# 8_CAN.net
KiCad netlist of a schematic drawn in EAGLE
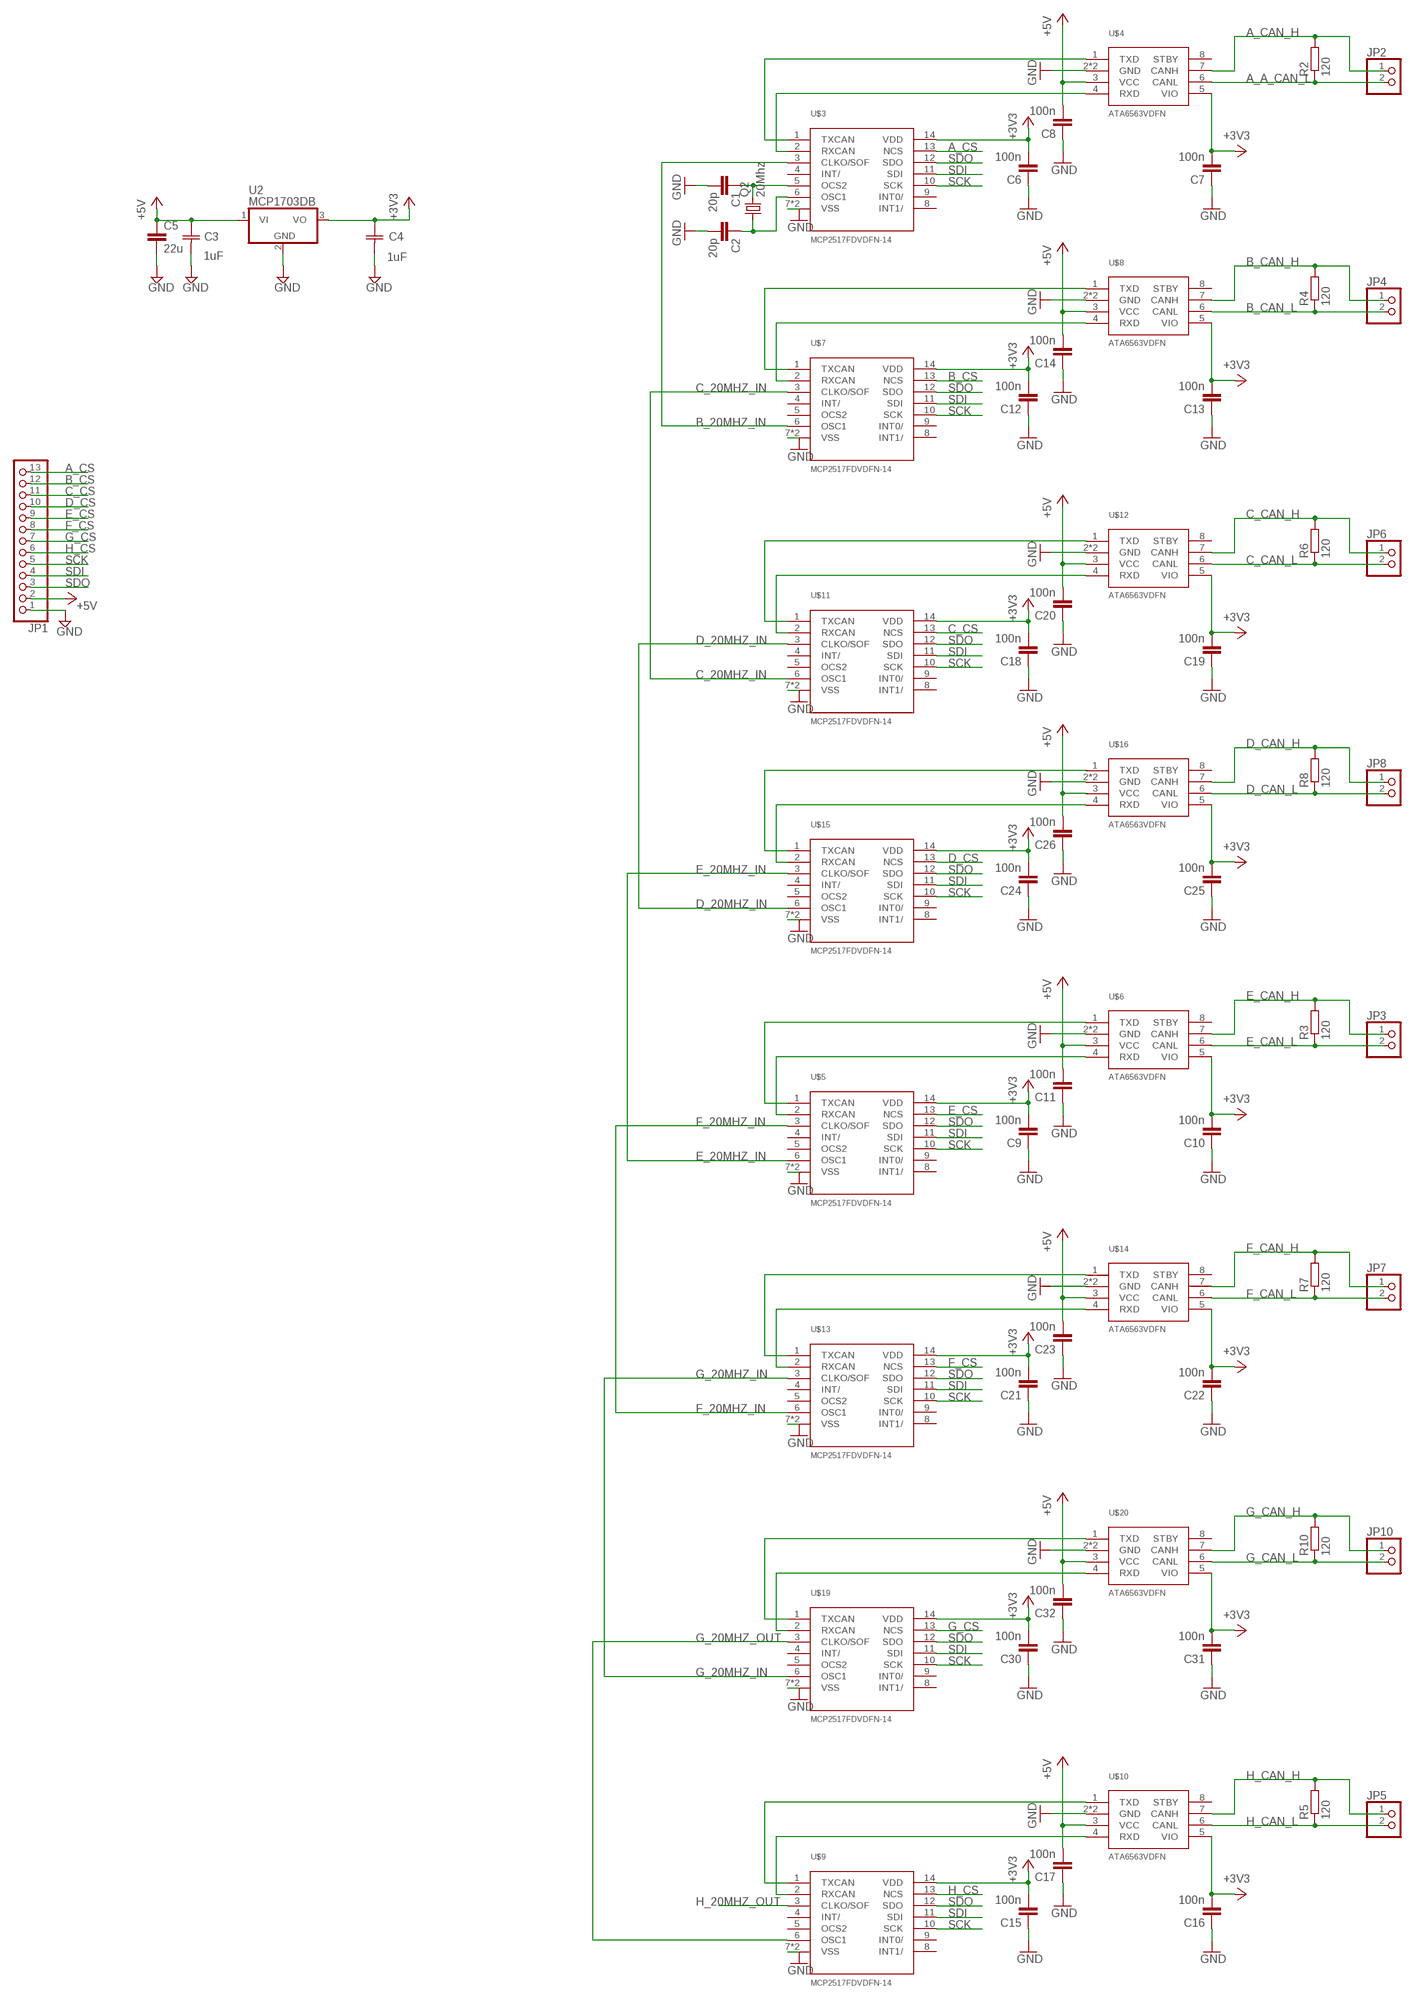
[diagram p0: schematic, sheet 1]

(export (version "E")
  (design (tool "Eeschema 10.0.6"))
  (components
    (comp (ref "C1")
      (value "20p")
      (footprint "eagle-import:C0402")
      (libsource (lib "eagle-import") (part "resistor_348_C-EUC0402"))
    )
    (comp (ref "C2")
      (value "20p")
      (footprint "eagle-import:C0402")
      (libsource (lib "eagle-import") (part "resistor_348_C-EUC0402"))
    )
    (comp (ref "C3")
      (value "1uF")
      (footprint "eagle-import:CAPC2013X140N")
      (fields (field (name "MPN") "C0805C105K3RACTU") (field (name "TOLERANCE") "±10%"))
      (libsource (lib "eagle-import") (part "C0805C105K3RACTU"))
    )
    (comp (ref "C4")
      (value "1uF")
      (footprint "eagle-import:CAPC2013X140N")
      (fields (field (name "MPN") "C0805C105K3RACTU") (field (name "TOLERANCE") "±10%"))
      (libsource (lib "eagle-import") (part "C0805C105K3RACTU"))
    )
    (comp (ref "C5")
      (value "22u")
      (footprint "eagle-import:C1206")
      (libsource (lib "eagle-import") (part "C-EUC1206"))
    )
    (comp (ref "C6")
      (value "100n")
      (footprint "eagle-import:C0402")
      (libsource (lib "eagle-import") (part "resistor_348_C-EUC0402"))
    )
    (comp (ref "C7")
      (value "100n")
      (footprint "eagle-import:C0402")
      (libsource (lib "eagle-import") (part "resistor_348_C-EUC0402"))
    )
    (comp (ref "C8")
      (value "100n")
      (footprint "eagle-import:C0402")
      (libsource (lib "eagle-import") (part "resistor_348_C-EUC0402"))
    )
    (comp (ref "C9")
      (value "100n")
      (footprint "eagle-import:C0402")
      (libsource (lib "eagle-import") (part "resistor_348_C-EUC0402"))
    )
    (comp (ref "C10")
      (value "100n")
      (footprint "eagle-import:C0402")
      (libsource (lib "eagle-import") (part "resistor_348_C-EUC0402"))
    )
    (comp (ref "C11")
      (value "100n")
      (footprint "eagle-import:C0402")
      (libsource (lib "eagle-import") (part "resistor_348_C-EUC0402"))
    )
    (comp (ref "C12")
      (value "100n")
      (footprint "eagle-import:C0402")
      (libsource (lib "eagle-import") (part "resistor_348_C-EUC0402"))
    )
    (comp (ref "C13")
      (value "100n")
      (footprint "eagle-import:C0402")
      (libsource (lib "eagle-import") (part "resistor_348_C-EUC0402"))
    )
    (comp (ref "C14")
      (value "100n")
      (footprint "eagle-import:C0402")
      (libsource (lib "eagle-import") (part "resistor_348_C-EUC0402"))
    )
    (comp (ref "C15")
      (value "100n")
      (footprint "eagle-import:C0402")
      (libsource (lib "eagle-import") (part "resistor_348_C-EUC0402"))
    )
    (comp (ref "C16")
      (value "100n")
      (footprint "eagle-import:C0402")
      (libsource (lib "eagle-import") (part "resistor_348_C-EUC0402"))
    )
    (comp (ref "C17")
      (value "100n")
      (footprint "eagle-import:C0402")
      (libsource (lib "eagle-import") (part "resistor_348_C-EUC0402"))
    )
    (comp (ref "C18")
      (value "100n")
      (footprint "eagle-import:C0402")
      (libsource (lib "eagle-import") (part "resistor_348_C-EUC0402"))
    )
    (comp (ref "C19")
      (value "100n")
      (footprint "eagle-import:C0402")
      (libsource (lib "eagle-import") (part "resistor_348_C-EUC0402"))
    )
    (comp (ref "C20")
      (value "100n")
      (footprint "eagle-import:C0402")
      (libsource (lib "eagle-import") (part "resistor_348_C-EUC0402"))
    )
    (comp (ref "C21")
      (value "100n")
      (footprint "eagle-import:C0402")
      (libsource (lib "eagle-import") (part "resistor_348_C-EUC0402"))
    )
    (comp (ref "C22")
      (value "100n")
      (footprint "eagle-import:C0402")
      (libsource (lib "eagle-import") (part "resistor_348_C-EUC0402"))
    )
    (comp (ref "C23")
      (value "100n")
      (footprint "eagle-import:C0402")
      (libsource (lib "eagle-import") (part "resistor_348_C-EUC0402"))
    )
    (comp (ref "C24")
      (value "100n")
      (footprint "eagle-import:C0402")
      (libsource (lib "eagle-import") (part "resistor_348_C-EUC0402"))
    )
    (comp (ref "C25")
      (value "100n")
      (footprint "eagle-import:C0402")
      (libsource (lib "eagle-import") (part "resistor_348_C-EUC0402"))
    )
    (comp (ref "C26")
      (value "100n")
      (footprint "eagle-import:C0402")
      (libsource (lib "eagle-import") (part "resistor_348_C-EUC0402"))
    )
    (comp (ref "C30")
      (value "100n")
      (footprint "eagle-import:C0402")
      (libsource (lib "eagle-import") (part "resistor_348_C-EUC0402"))
    )
    (comp (ref "C31")
      (value "100n")
      (footprint "eagle-import:C0402")
      (libsource (lib "eagle-import") (part "resistor_348_C-EUC0402"))
    )
    (comp (ref "C32")
      (value "100n")
      (footprint "eagle-import:C0402")
      (libsource (lib "eagle-import") (part "resistor_348_C-EUC0402"))
    )
    (comp (ref "JP1")
      (value "PINHD-1X13")
      (footprint "eagle-import:1X13")
      (libsource (lib "eagle-import") (part "PINHD-1X13"))
    )
    (comp (ref "JP2")
      (value "PINHD-1X2")
      (footprint "eagle-import:1X02")
      (libsource (lib "eagle-import") (part "PINHD-1X2"))
    )
    (comp (ref "JP3")
      (value "PINHD-1X2")
      (footprint "eagle-import:1X02")
      (libsource (lib "eagle-import") (part "PINHD-1X2"))
    )
    (comp (ref "JP4")
      (value "PINHD-1X2")
      (footprint "eagle-import:1X02")
      (libsource (lib "eagle-import") (part "PINHD-1X2"))
    )
    (comp (ref "JP5")
      (value "PINHD-1X2")
      (footprint "eagle-import:1X02")
      (libsource (lib "eagle-import") (part "PINHD-1X2"))
    )
    (comp (ref "JP6")
      (value "PINHD-1X2")
      (footprint "eagle-import:1X02")
      (libsource (lib "eagle-import") (part "PINHD-1X2"))
    )
    (comp (ref "JP7")
      (value "PINHD-1X2")
      (footprint "eagle-import:1X02")
      (libsource (lib "eagle-import") (part "PINHD-1X2"))
    )
    (comp (ref "JP8")
      (value "PINHD-1X2")
      (footprint "eagle-import:1X02")
      (libsource (lib "eagle-import") (part "PINHD-1X2"))
    )
    (comp (ref "JP10")
      (value "PINHD-1X2")
      (footprint "eagle-import:1X02")
      (libsource (lib "eagle-import") (part "PINHD-1X2"))
    )
    (comp (ref "Q2")
      (value "20Mhz")
      (footprint "eagle-import:CTS406")
      (libsource (lib "eagle-import") (part "CRYSTALCTS406"))
    )
    (comp (ref "R2")
      (value "120")
      (footprint "eagle-import:R0402")
      (libsource (lib "eagle-import") (part "R-EU_R0402"))
    )
    (comp (ref "R3")
      (value "120")
      (footprint "eagle-import:R0402")
      (libsource (lib "eagle-import") (part "R-EU_R0402"))
    )
    (comp (ref "R4")
      (value "120")
      (footprint "eagle-import:R0402")
      (libsource (lib "eagle-import") (part "R-EU_R0402"))
    )
    (comp (ref "R5")
      (value "120")
      (footprint "eagle-import:R0402")
      (libsource (lib "eagle-import") (part "R-EU_R0402"))
    )
    (comp (ref "R6")
      (value "120")
      (footprint "eagle-import:R0402")
      (libsource (lib "eagle-import") (part "R-EU_R0402"))
    )
    (comp (ref "R7")
      (value "120")
      (footprint "eagle-import:R0402")
      (libsource (lib "eagle-import") (part "R-EU_R0402"))
    )
    (comp (ref "R8")
      (value "120")
      (footprint "eagle-import:R0402")
      (libsource (lib "eagle-import") (part "R-EU_R0402"))
    )
    (comp (ref "R10")
      (value "120")
      (footprint "eagle-import:R0402")
      (libsource (lib "eagle-import") (part "R-EU_R0402"))
    )
    (comp (ref "U$3")
      (value "MCP2517FDVDFN-14")
      (footprint "eagle-import:VDFN-14_4.5X3")
      (libsource (lib "eagle-import") (part "MCP2517FDVDFN-14"))
    )
    (comp (ref "U$4")
      (value "ATA6563VDFN")
      (footprint "eagle-import:VDFN-8_3X3")
      (libsource (lib "eagle-import") (part "ATA6563VDFN"))
    )
    (comp (ref "U$5")
      (value "MCP2517FDVDFN-14")
      (footprint "eagle-import:VDFN-14_4.5X3")
      (libsource (lib "eagle-import") (part "MCP2517FDVDFN-14"))
    )
    (comp (ref "U$6")
      (value "ATA6563VDFN")
      (footprint "eagle-import:VDFN-8_3X3")
      (libsource (lib "eagle-import") (part "ATA6563VDFN"))
    )
    (comp (ref "U$7")
      (value "MCP2517FDVDFN-14")
      (footprint "eagle-import:VDFN-14_4.5X3")
      (libsource (lib "eagle-import") (part "MCP2517FDVDFN-14"))
    )
    (comp (ref "U$8")
      (value "ATA6563VDFN")
      (footprint "eagle-import:VDFN-8_3X3")
      (libsource (lib "eagle-import") (part "ATA6563VDFN"))
    )
    (comp (ref "U$9")
      (value "MCP2517FDVDFN-14")
      (footprint "eagle-import:VDFN-14_4.5X3")
      (libsource (lib "eagle-import") (part "MCP2517FDVDFN-14"))
    )
    (comp (ref "U$10")
      (value "ATA6563VDFN")
      (footprint "eagle-import:VDFN-8_3X3")
      (libsource (lib "eagle-import") (part "ATA6563VDFN"))
    )
    (comp (ref "U$11")
      (value "MCP2517FDVDFN-14")
      (footprint "eagle-import:VDFN-14_4.5X3")
      (libsource (lib "eagle-import") (part "MCP2517FDVDFN-14"))
    )
    (comp (ref "U$12")
      (value "ATA6563VDFN")
      (footprint "eagle-import:VDFN-8_3X3")
      (libsource (lib "eagle-import") (part "ATA6563VDFN"))
    )
    (comp (ref "U$13")
      (value "MCP2517FDVDFN-14")
      (footprint "eagle-import:VDFN-14_4.5X3")
      (libsource (lib "eagle-import") (part "MCP2517FDVDFN-14"))
    )
    (comp (ref "U$14")
      (value "ATA6563VDFN")
      (footprint "eagle-import:VDFN-8_3X3")
      (libsource (lib "eagle-import") (part "ATA6563VDFN"))
    )
    (comp (ref "U$15")
      (value "MCP2517FDVDFN-14")
      (footprint "eagle-import:VDFN-14_4.5X3")
      (libsource (lib "eagle-import") (part "MCP2517FDVDFN-14"))
    )
    (comp (ref "U$16")
      (value "ATA6563VDFN")
      (footprint "eagle-import:VDFN-8_3X3")
      (libsource (lib "eagle-import") (part "ATA6563VDFN"))
    )
    (comp (ref "U$19")
      (value "MCP2517FDVDFN-14")
      (footprint "eagle-import:VDFN-14_4.5X3")
      (libsource (lib "eagle-import") (part "MCP2517FDVDFN-14"))
    )
    (comp (ref "U$20")
      (value "ATA6563VDFN")
      (footprint "eagle-import:VDFN-8_3X3")
      (libsource (lib "eagle-import") (part "ATA6563VDFN"))
    )
    (comp (ref "U2")
      (value "MCP1703DB")
      (footprint "eagle-import:SOT223")
      (libsource (lib "eagle-import") (part "MCP1703DB"))
    )
  )
  (nets
    (net (code "1") (name "+3V3") (class "Default")
      (node (ref "C10") (pin "2") (pinfunction "2_2") (pintype "passive"))
      (node (ref "C12") (pin "2") (pinfunction "2_2") (pintype "passive"))
      (node (ref "C13") (pin "2") (pinfunction "2_2") (pintype "passive"))
      (node (ref "C15") (pin "2") (pinfunction "2_2") (pintype "passive"))
      (node (ref "C16") (pin "2") (pinfunction "2_2") (pintype "passive"))
      (node (ref "C18") (pin "2") (pinfunction "2_2") (pintype "passive"))
      (node (ref "C19") (pin "2") (pinfunction "2_2") (pintype "passive"))
      (node (ref "C21") (pin "2") (pinfunction "2_2") (pintype "passive"))
      (node (ref "C22") (pin "2") (pinfunction "2_2") (pintype "passive"))
      (node (ref "C24") (pin "2") (pinfunction "2_2") (pintype "passive"))
      (node (ref "C25") (pin "2") (pinfunction "2_2") (pintype "passive"))
      (node (ref "C30") (pin "2") (pinfunction "2_2") (pintype "passive"))
      (node (ref "C31") (pin "2") (pinfunction "2_2") (pintype "passive"))
      (node (ref "C4") (pin "1") (pinfunction "C1_1") (pintype "passive"))
      (node (ref "C6") (pin "2") (pinfunction "2_2") (pintype "passive"))
      (node (ref "C7") (pin "2") (pinfunction "2_2") (pintype "passive"))
      (node (ref "C9") (pin "2") (pinfunction "2_2") (pintype "passive"))
      (node (ref "U$10") (pin "5") (pinfunction "VIO_5") (pintype "bidirectional"))
      (node (ref "U$11") (pin "14") (pinfunction "VDD_14") (pintype "bidirectional"))
      (node (ref "U$12") (pin "5") (pinfunction "VIO_5") (pintype "bidirectional"))
      (node (ref "U$13") (pin "14") (pinfunction "VDD_14") (pintype "bidirectional"))
      (node (ref "U$14") (pin "5") (pinfunction "VIO_5") (pintype "bidirectional"))
      (node (ref "U$15") (pin "14") (pinfunction "VDD_14") (pintype "bidirectional"))
      (node (ref "U$16") (pin "5") (pinfunction "VIO_5") (pintype "bidirectional"))
      (node (ref "U$19") (pin "14") (pinfunction "VDD_14") (pintype "bidirectional"))
      (node (ref "U$20") (pin "5") (pinfunction "VIO_5") (pintype "bidirectional"))
      (node (ref "U$3") (pin "14") (pinfunction "VDD_14") (pintype "bidirectional"))
      (node (ref "U$4") (pin "5") (pinfunction "VIO_5") (pintype "bidirectional"))
      (node (ref "U$5") (pin "14") (pinfunction "VDD_14") (pintype "bidirectional"))
      (node (ref "U$6") (pin "5") (pinfunction "VIO_5") (pintype "bidirectional"))
      (node (ref "U$7") (pin "14") (pinfunction "VDD_14") (pintype "bidirectional"))
      (node (ref "U$8") (pin "5") (pinfunction "VIO_5") (pintype "bidirectional"))
      (node (ref "U$9") (pin "14") (pinfunction "VDD_14") (pintype "bidirectional"))
      (node (ref "U2") (pin "3") (pinfunction "VO_3") (pintype "passive"))
    )
    (net (code "2") (name "+5V") (class "Default")
      (node (ref "C11") (pin "2") (pinfunction "2_2") (pintype "passive"))
      (node (ref "C14") (pin "2") (pinfunction "2_2") (pintype "passive"))
      (node (ref "C17") (pin "2") (pinfunction "2_2") (pintype "passive"))
      (node (ref "C20") (pin "2") (pinfunction "2_2") (pintype "passive"))
      (node (ref "C23") (pin "2") (pinfunction "2_2") (pintype "passive"))
      (node (ref "C26") (pin "2") (pinfunction "2_2") (pintype "passive"))
      (node (ref "C3") (pin "1") (pinfunction "C1_1") (pintype "passive"))
      (node (ref "C32") (pin "2") (pinfunction "2_2") (pintype "passive"))
      (node (ref "C5") (pin "1") (pinfunction "1_1") (pintype "passive"))
      (node (ref "C8") (pin "2") (pinfunction "2_2") (pintype "passive"))
      (node (ref "JP1") (pin "2") (pinfunction "2_2") (pintype "passive"))
      (node (ref "U$10") (pin "3") (pinfunction "VCC_3") (pintype "bidirectional"))
      (node (ref "U$12") (pin "3") (pinfunction "VCC_3") (pintype "bidirectional"))
      (node (ref "U$14") (pin "3") (pinfunction "VCC_3") (pintype "bidirectional"))
      (node (ref "U$16") (pin "3") (pinfunction "VCC_3") (pintype "bidirectional"))
      (node (ref "U$20") (pin "3") (pinfunction "VCC_3") (pintype "bidirectional"))
      (node (ref "U$4") (pin "3") (pinfunction "VCC_3") (pintype "bidirectional"))
      (node (ref "U$6") (pin "3") (pinfunction "VCC_3") (pintype "bidirectional"))
      (node (ref "U$8") (pin "3") (pinfunction "VCC_3") (pintype "bidirectional"))
      (node (ref "U2") (pin "1") (pinfunction "VI_1") (pintype "input"))
    )
    (net (code "3") (name "/A_A_CAN_L") (class "Default")
      (node (ref "JP2") (pin "2") (pinfunction "2_2") (pintype "passive"))
      (node (ref "R2") (pin "1") (pinfunction "1_1") (pintype "passive"))
      (node (ref "U$4") (pin "6") (pinfunction "CANL_6") (pintype "bidirectional"))
    )
    (net (code "4") (name "/A_CAN_H") (class "Default")
      (node (ref "JP2") (pin "1") (pinfunction "1_1") (pintype "passive"))
      (node (ref "R2") (pin "2") (pinfunction "2_2") (pintype "passive"))
      (node (ref "U$4") (pin "7") (pinfunction "CANH_7") (pintype "bidirectional"))
    )
    (net (code "5") (name "/A_CS") (class "Default")
      (node (ref "JP1") (pin "13") (pinfunction "13_13") (pintype "passive"))
      (node (ref "U$3") (pin "13") (pinfunction "NCS_13") (pintype "bidirectional"))
    )
    (net (code "6") (name "/B_20MHZ_IN") (class "Default")
      (node (ref "U$3") (pin "3") (pinfunction "CLKO/SOF_3") (pintype "bidirectional"))
      (node (ref "U$7") (pin "6") (pinfunction "OSC1_6") (pintype "bidirectional"))
    )
    (net (code "7") (name "/B_CAN_H") (class "Default")
      (node (ref "JP4") (pin "1") (pinfunction "1_1") (pintype "passive"))
      (node (ref "R4") (pin "2") (pinfunction "2_2") (pintype "passive"))
      (node (ref "U$8") (pin "7") (pinfunction "CANH_7") (pintype "bidirectional"))
    )
    (net (code "8") (name "/B_CAN_L") (class "Default")
      (node (ref "JP4") (pin "2") (pinfunction "2_2") (pintype "passive"))
      (node (ref "R4") (pin "1") (pinfunction "1_1") (pintype "passive"))
      (node (ref "U$8") (pin "6") (pinfunction "CANL_6") (pintype "bidirectional"))
    )
    (net (code "9") (name "/B_CS") (class "Default")
      (node (ref "JP1") (pin "12") (pinfunction "12_12") (pintype "passive"))
      (node (ref "U$7") (pin "13") (pinfunction "NCS_13") (pintype "bidirectional"))
    )
    (net (code "10") (name "/C_20MHZ_IN") (class "Default")
      (node (ref "U$11") (pin "6") (pinfunction "OSC1_6") (pintype "bidirectional"))
      (node (ref "U$7") (pin "3") (pinfunction "CLKO/SOF_3") (pintype "bidirectional"))
    )
    (net (code "11") (name "/C_CAN_H") (class "Default")
      (node (ref "JP6") (pin "1") (pinfunction "1_1") (pintype "passive"))
      (node (ref "R6") (pin "2") (pinfunction "2_2") (pintype "passive"))
      (node (ref "U$12") (pin "7") (pinfunction "CANH_7") (pintype "bidirectional"))
    )
    (net (code "12") (name "/C_CAN_L") (class "Default")
      (node (ref "JP6") (pin "2") (pinfunction "2_2") (pintype "passive"))
      (node (ref "R6") (pin "1") (pinfunction "1_1") (pintype "passive"))
      (node (ref "U$12") (pin "6") (pinfunction "CANL_6") (pintype "bidirectional"))
    )
    (net (code "13") (name "/C_CS") (class "Default")
      (node (ref "JP1") (pin "11") (pinfunction "11_11") (pintype "passive"))
      (node (ref "U$11") (pin "13") (pinfunction "NCS_13") (pintype "bidirectional"))
    )
    (net (code "14") (name "/D_20MHZ_IN") (class "Default")
      (node (ref "U$11") (pin "3") (pinfunction "CLKO/SOF_3") (pintype "bidirectional"))
      (node (ref "U$15") (pin "6") (pinfunction "OSC1_6") (pintype "bidirectional"))
    )
    (net (code "15") (name "/D_CAN_H") (class "Default")
      (node (ref "JP8") (pin "1") (pinfunction "1_1") (pintype "passive"))
      (node (ref "R8") (pin "2") (pinfunction "2_2") (pintype "passive"))
      (node (ref "U$16") (pin "7") (pinfunction "CANH_7") (pintype "bidirectional"))
    )
    (net (code "16") (name "/D_CAN_L") (class "Default")
      (node (ref "JP8") (pin "2") (pinfunction "2_2") (pintype "passive"))
      (node (ref "R8") (pin "1") (pinfunction "1_1") (pintype "passive"))
      (node (ref "U$16") (pin "6") (pinfunction "CANL_6") (pintype "bidirectional"))
    )
    (net (code "17") (name "/D_CS") (class "Default")
      (node (ref "JP1") (pin "10") (pinfunction "10_10") (pintype "passive"))
      (node (ref "U$15") (pin "13") (pinfunction "NCS_13") (pintype "bidirectional"))
    )
    (net (code "18") (name "/E_20MHZ_IN") (class "Default")
      (node (ref "U$15") (pin "3") (pinfunction "CLKO/SOF_3") (pintype "bidirectional"))
      (node (ref "U$5") (pin "6") (pinfunction "OSC1_6") (pintype "bidirectional"))
    )
    (net (code "19") (name "/E_CAN_H") (class "Default")
      (node (ref "JP3") (pin "1") (pinfunction "1_1") (pintype "passive"))
      (node (ref "R3") (pin "2") (pinfunction "2_2") (pintype "passive"))
      (node (ref "U$6") (pin "7") (pinfunction "CANH_7") (pintype "bidirectional"))
    )
    (net (code "20") (name "/E_CAN_L") (class "Default")
      (node (ref "JP3") (pin "2") (pinfunction "2_2") (pintype "passive"))
      (node (ref "R3") (pin "1") (pinfunction "1_1") (pintype "passive"))
      (node (ref "U$6") (pin "6") (pinfunction "CANL_6") (pintype "bidirectional"))
    )
    (net (code "21") (name "/E_CS") (class "Default")
      (node (ref "JP1") (pin "9") (pinfunction "9_9") (pintype "passive"))
      (node (ref "U$5") (pin "13") (pinfunction "NCS_13") (pintype "bidirectional"))
    )
    (net (code "22") (name "/F_20MHZ_IN") (class "Default")
      (node (ref "U$13") (pin "6") (pinfunction "OSC1_6") (pintype "bidirectional"))
      (node (ref "U$5") (pin "3") (pinfunction "CLKO/SOF_3") (pintype "bidirectional"))
    )
    (net (code "23") (name "/F_CAN_H") (class "Default")
      (node (ref "JP7") (pin "1") (pinfunction "1_1") (pintype "passive"))
      (node (ref "R7") (pin "2") (pinfunction "2_2") (pintype "passive"))
      (node (ref "U$14") (pin "7") (pinfunction "CANH_7") (pintype "bidirectional"))
    )
    (net (code "24") (name "/F_CAN_L") (class "Default")
      (node (ref "JP7") (pin "2") (pinfunction "2_2") (pintype "passive"))
      (node (ref "R7") (pin "1") (pinfunction "1_1") (pintype "passive"))
      (node (ref "U$14") (pin "6") (pinfunction "CANL_6") (pintype "bidirectional"))
    )
    (net (code "25") (name "/F_CS") (class "Default")
      (node (ref "JP1") (pin "8") (pinfunction "8_8") (pintype "passive"))
      (node (ref "U$13") (pin "13") (pinfunction "NCS_13") (pintype "bidirectional"))
    )
    (net (code "26") (name "/G_20MHZ_IN") (class "Default")
      (node (ref "U$13") (pin "3") (pinfunction "CLKO/SOF_3") (pintype "bidirectional"))
      (node (ref "U$19") (pin "6") (pinfunction "OSC1_6") (pintype "bidirectional"))
    )
    (net (code "27") (name "/G_20MHZ_OUT") (class "Default")
      (node (ref "U$19") (pin "3") (pinfunction "CLKO/SOF_3") (pintype "bidirectional"))
      (node (ref "U$9") (pin "6") (pinfunction "OSC1_6") (pintype "bidirectional"))
    )
    (net (code "28") (name "/G_CAN_H") (class "Default")
      (node (ref "JP10") (pin "1") (pinfunction "1_1") (pintype "passive"))
      (node (ref "R10") (pin "2") (pinfunction "2_2") (pintype "passive"))
      (node (ref "U$20") (pin "7") (pinfunction "CANH_7") (pintype "bidirectional"))
    )
    (net (code "29") (name "/G_CAN_L") (class "Default")
      (node (ref "JP10") (pin "2") (pinfunction "2_2") (pintype "passive"))
      (node (ref "R10") (pin "1") (pinfunction "1_1") (pintype "passive"))
      (node (ref "U$20") (pin "6") (pinfunction "CANL_6") (pintype "bidirectional"))
    )
    (net (code "30") (name "/G_CS") (class "Default")
      (node (ref "JP1") (pin "7") (pinfunction "7_7") (pintype "passive"))
      (node (ref "U$19") (pin "13") (pinfunction "NCS_13") (pintype "bidirectional"))
    )
    (net (code "31") (name "/H_20MHZ_OUT") (class "Default")
      (node (ref "U$9") (pin "3") (pinfunction "CLKO/SOF_3") (pintype "bidirectional"))
    )
    (net (code "32") (name "/H_CAN_H") (class "Default")
      (node (ref "JP5") (pin "1") (pinfunction "1_1") (pintype "passive"))
      (node (ref "R5") (pin "2") (pinfunction "2_2") (pintype "passive"))
      (node (ref "U$10") (pin "7") (pinfunction "CANH_7") (pintype "bidirectional"))
    )
    (net (code "33") (name "/H_CAN_L") (class "Default")
      (node (ref "JP5") (pin "2") (pinfunction "2_2") (pintype "passive"))
      (node (ref "R5") (pin "1") (pinfunction "1_1") (pintype "passive"))
      (node (ref "U$10") (pin "6") (pinfunction "CANL_6") (pintype "bidirectional"))
    )
    (net (code "34") (name "/H_CS") (class "Default")
      (node (ref "JP1") (pin "6") (pinfunction "6_6") (pintype "passive"))
      (node (ref "U$9") (pin "13") (pinfunction "NCS_13") (pintype "bidirectional"))
    )
    (net (code "35") (name "/SCK") (class "Default")
      (node (ref "JP1") (pin "5") (pinfunction "5_5") (pintype "passive"))
      (node (ref "U$11") (pin "10") (pinfunction "SCK_10") (pintype "bidirectional"))
      (node (ref "U$13") (pin "10") (pinfunction "SCK_10") (pintype "bidirectional"))
      (node (ref "U$15") (pin "10") (pinfunction "SCK_10") (pintype "bidirectional"))
      (node (ref "U$19") (pin "10") (pinfunction "SCK_10") (pintype "bidirectional"))
      (node (ref "U$3") (pin "10") (pinfunction "SCK_10") (pintype "bidirectional"))
      (node (ref "U$5") (pin "10") (pinfunction "SCK_10") (pintype "bidirectional"))
      (node (ref "U$7") (pin "10") (pinfunction "SCK_10") (pintype "bidirectional"))
      (node (ref "U$9") (pin "10") (pinfunction "SCK_10") (pintype "bidirectional"))
    )
    (net (code "36") (name "/SDI") (class "Default")
      (node (ref "JP1") (pin "4") (pinfunction "4_4") (pintype "passive"))
      (node (ref "U$11") (pin "11") (pinfunction "SDI_11") (pintype "bidirectional"))
      (node (ref "U$13") (pin "11") (pinfunction "SDI_11") (pintype "bidirectional"))
      (node (ref "U$15") (pin "11") (pinfunction "SDI_11") (pintype "bidirectional"))
      (node (ref "U$19") (pin "11") (pinfunction "SDI_11") (pintype "bidirectional"))
      (node (ref "U$3") (pin "11") (pinfunction "SDI_11") (pintype "bidirectional"))
      (node (ref "U$5") (pin "11") (pinfunction "SDI_11") (pintype "bidirectional"))
      (node (ref "U$7") (pin "11") (pinfunction "SDI_11") (pintype "bidirectional"))
      (node (ref "U$9") (pin "11") (pinfunction "SDI_11") (pintype "bidirectional"))
    )
    (net (code "37") (name "/SDO") (class "Default")
      (node (ref "JP1") (pin "3") (pinfunction "3_3") (pintype "passive"))
      (node (ref "U$11") (pin "12") (pinfunction "SDO_12") (pintype "bidirectional"))
      (node (ref "U$13") (pin "12") (pinfunction "SDO_12") (pintype "bidirectional"))
      (node (ref "U$15") (pin "12") (pinfunction "SDO_12") (pintype "bidirectional"))
      (node (ref "U$19") (pin "12") (pinfunction "SDO_12") (pintype "bidirectional"))
      (node (ref "U$3") (pin "12") (pinfunction "SDO_12") (pintype "bidirectional"))
      (node (ref "U$5") (pin "12") (pinfunction "SDO_12") (pintype "bidirectional"))
      (node (ref "U$7") (pin "12") (pinfunction "SDO_12") (pintype "bidirectional"))
      (node (ref "U$9") (pin "12") (pinfunction "SDO_12") (pintype "bidirectional"))
    )
    (net (code "38") (name "GND") (class "Default")
      (node (ref "C1") (pin "2") (pinfunction "2_2") (pintype "passive"))
      (node (ref "C10") (pin "1") (pinfunction "1_1") (pintype "passive"))
      (node (ref "C11") (pin "1") (pinfunction "1_1") (pintype "passive"))
      (node (ref "C12") (pin "1") (pinfunction "1_1") (pintype "passive"))
      (node (ref "C13") (pin "1") (pinfunction "1_1") (pintype "passive"))
      (node (ref "C14") (pin "1") (pinfunction "1_1") (pintype "passive"))
      (node (ref "C15") (pin "1") (pinfunction "1_1") (pintype "passive"))
      (node (ref "C16") (pin "1") (pinfunction "1_1") (pintype "passive"))
      (node (ref "C17") (pin "1") (pinfunction "1_1") (pintype "passive"))
      (node (ref "C18") (pin "1") (pinfunction "1_1") (pintype "passive"))
      (node (ref "C19") (pin "1") (pinfunction "1_1") (pintype "passive"))
      (node (ref "C2") (pin "2") (pinfunction "2_2") (pintype "passive"))
      (node (ref "C20") (pin "1") (pinfunction "1_1") (pintype "passive"))
      (node (ref "C21") (pin "1") (pinfunction "1_1") (pintype "passive"))
      (node (ref "C22") (pin "1") (pinfunction "1_1") (pintype "passive"))
      (node (ref "C23") (pin "1") (pinfunction "1_1") (pintype "passive"))
      (node (ref "C24") (pin "1") (pinfunction "1_1") (pintype "passive"))
      (node (ref "C25") (pin "1") (pinfunction "1_1") (pintype "passive"))
      (node (ref "C26") (pin "1") (pinfunction "1_1") (pintype "passive"))
      (node (ref "C3") (pin "2") (pinfunction "C2_2") (pintype "passive"))
      (node (ref "C30") (pin "1") (pinfunction "1_1") (pintype "passive"))
      (node (ref "C31") (pin "1") (pinfunction "1_1") (pintype "passive"))
      (node (ref "C32") (pin "1") (pinfunction "1_1") (pintype "passive"))
      (node (ref "C4") (pin "2") (pinfunction "C2_2") (pintype "passive"))
      (node (ref "C5") (pin "2") (pinfunction "2_2") (pintype "passive"))
      (node (ref "C6") (pin "1") (pinfunction "1_1") (pintype "passive"))
      (node (ref "C7") (pin "1") (pinfunction "1_1") (pintype "passive"))
      (node (ref "C8") (pin "1") (pinfunction "1_1") (pintype "passive"))
      (node (ref "C9") (pin "1") (pinfunction "1_1") (pintype "passive"))
      (node (ref "JP1") (pin "1") (pinfunction "1_1") (pintype "passive"))
      (node (ref "U$10") (pin "2") (pinfunction "GND_2") (pintype "bidirectional"))
      (node (ref "U$10") (pin "9") (pinfunction "GND_9") (pintype "bidirectional"))
      (node (ref "U$11") (pin "15") (pinfunction "VSS_15") (pintype "bidirectional"))
      (node (ref "U$11") (pin "7") (pinfunction "VSS_7") (pintype "bidirectional"))
      (node (ref "U$12") (pin "2") (pinfunction "GND_2") (pintype "bidirectional"))
      (node (ref "U$12") (pin "9") (pinfunction "GND_9") (pintype "bidirectional"))
      (node (ref "U$13") (pin "15") (pinfunction "VSS_15") (pintype "bidirectional"))
      (node (ref "U$13") (pin "7") (pinfunction "VSS_7") (pintype "bidirectional"))
      (node (ref "U$14") (pin "2") (pinfunction "GND_2") (pintype "bidirectional"))
      (node (ref "U$14") (pin "9") (pinfunction "GND_9") (pintype "bidirectional"))
      (node (ref "U$15") (pin "15") (pinfunction "VSS_15") (pintype "bidirectional"))
      (node (ref "U$15") (pin "7") (pinfunction "VSS_7") (pintype "bidirectional"))
      (node (ref "U$16") (pin "2") (pinfunction "GND_2") (pintype "bidirectional"))
      (node (ref "U$16") (pin "9") (pinfunction "GND_9") (pintype "bidirectional"))
      (node (ref "U$19") (pin "15") (pinfunction "VSS_15") (pintype "bidirectional"))
      (node (ref "U$19") (pin "7") (pinfunction "VSS_7") (pintype "bidirectional"))
      (node (ref "U$20") (pin "2") (pinfunction "GND_2") (pintype "bidirectional"))
      (node (ref "U$20") (pin "9") (pinfunction "GND_9") (pintype "bidirectional"))
      (node (ref "U$3") (pin "15") (pinfunction "VSS_15") (pintype "bidirectional"))
      (node (ref "U$3") (pin "7") (pinfunction "VSS_7") (pintype "bidirectional"))
      (node (ref "U$4") (pin "2") (pinfunction "GND_2") (pintype "bidirectional"))
      (node (ref "U$4") (pin "9") (pinfunction "GND_9") (pintype "bidirectional"))
      (node (ref "U$5") (pin "15") (pinfunction "VSS_15") (pintype "bidirectional"))
      (node (ref "U$5") (pin "7") (pinfunction "VSS_7") (pintype "bidirectional"))
      (node (ref "U$6") (pin "2") (pinfunction "GND_2") (pintype "bidirectional"))
      (node (ref "U$6") (pin "9") (pinfunction "GND_9") (pintype "bidirectional"))
      (node (ref "U$7") (pin "15") (pinfunction "VSS_15") (pintype "bidirectional"))
      (node (ref "U$7") (pin "7") (pinfunction "VSS_7") (pintype "bidirectional"))
      (node (ref "U$8") (pin "2") (pinfunction "GND_2") (pintype "bidirectional"))
      (node (ref "U$8") (pin "9") (pinfunction "GND_9") (pintype "bidirectional"))
      (node (ref "U$9") (pin "15") (pinfunction "VSS_15") (pintype "bidirectional"))
      (node (ref "U$9") (pin "7") (pinfunction "VSS_7") (pintype "bidirectional"))
      (node (ref "U2") (pin "2") (pinfunction "GND_2") (pintype "passive"))
    )
    (net (code "39") (name "Net-(Q2-2)") (class "Default")
      (node (ref "C1") (pin "1") (pinfunction "1_1") (pintype "passive"))
      (node (ref "Q2") (pin "3") (pinfunction "2_3") (pintype "passive"))
      (node (ref "U$3") (pin "5") (pinfunction "OCS2_5") (pintype "bidirectional"))
    )
    (net (code "40") (name "Net-(U$3-OSC1)") (class "Default")
      (node (ref "C2") (pin "1") (pinfunction "1_1") (pintype "passive"))
      (node (ref "Q2") (pin "1") (pinfunction "1_1") (pintype "passive"))
      (node (ref "U$3") (pin "6") (pinfunction "OSC1_6") (pintype "bidirectional"))
    )
    (net (code "41") (name "Net-(U$3-RXCAN)") (class "Default")
      (node (ref "U$3") (pin "2") (pinfunction "RXCAN_2") (pintype "bidirectional"))
      (node (ref "U$4") (pin "4") (pinfunction "RXD_4") (pintype "bidirectional"))
    )
    (net (code "42") (name "Net-(U$3-TXCAN)") (class "Default")
      (node (ref "U$3") (pin "1") (pinfunction "TXCAN_1") (pintype "bidirectional"))
      (node (ref "U$4") (pin "1") (pinfunction "TXD_1") (pintype "bidirectional"))
    )
    (net (code "43") (name "Net-(U$5-RXCAN)") (class "Default")
      (node (ref "U$5") (pin "2") (pinfunction "RXCAN_2") (pintype "bidirectional"))
      (node (ref "U$6") (pin "4") (pinfunction "RXD_4") (pintype "bidirectional"))
    )
    (net (code "44") (name "Net-(U$5-TXCAN)") (class "Default")
      (node (ref "U$5") (pin "1") (pinfunction "TXCAN_1") (pintype "bidirectional"))
      (node (ref "U$6") (pin "1") (pinfunction "TXD_1") (pintype "bidirectional"))
    )
    (net (code "45") (name "Net-(U$7-RXCAN)") (class "Default")
      (node (ref "U$7") (pin "2") (pinfunction "RXCAN_2") (pintype "bidirectional"))
      (node (ref "U$8") (pin "4") (pinfunction "RXD_4") (pintype "bidirectional"))
    )
    (net (code "46") (name "Net-(U$7-TXCAN)") (class "Default")
      (node (ref "U$7") (pin "1") (pinfunction "TXCAN_1") (pintype "bidirectional"))
      (node (ref "U$8") (pin "1") (pinfunction "TXD_1") (pintype "bidirectional"))
    )
    (net (code "47") (name "Net-(U$10-RXD)") (class "Default")
      (node (ref "U$10") (pin "4") (pinfunction "RXD_4") (pintype "bidirectional"))
      (node (ref "U$9") (pin "2") (pinfunction "RXCAN_2") (pintype "bidirectional"))
    )
    (net (code "48") (name "Net-(U$10-TXD)") (class "Default")
      (node (ref "U$10") (pin "1") (pinfunction "TXD_1") (pintype "bidirectional"))
      (node (ref "U$9") (pin "1") (pinfunction "TXCAN_1") (pintype "bidirectional"))
    )
    (net (code "49") (name "Net-(U$11-RXCAN)") (class "Default")
      (node (ref "U$11") (pin "2") (pinfunction "RXCAN_2") (pintype "bidirectional"))
      (node (ref "U$12") (pin "4") (pinfunction "RXD_4") (pintype "bidirectional"))
    )
    (net (code "50") (name "Net-(U$11-TXCAN)") (class "Default")
      (node (ref "U$11") (pin "1") (pinfunction "TXCAN_1") (pintype "bidirectional"))
      (node (ref "U$12") (pin "1") (pinfunction "TXD_1") (pintype "bidirectional"))
    )
    (net (code "51") (name "Net-(U$13-RXCAN)") (class "Default")
      (node (ref "U$13") (pin "2") (pinfunction "RXCAN_2") (pintype "bidirectional"))
      (node (ref "U$14") (pin "4") (pinfunction "RXD_4") (pintype "bidirectional"))
    )
    (net (code "52") (name "Net-(U$13-TXCAN)") (class "Default")
      (node (ref "U$13") (pin "1") (pinfunction "TXCAN_1") (pintype "bidirectional"))
      (node (ref "U$14") (pin "1") (pinfunction "TXD_1") (pintype "bidirectional"))
    )
    (net (code "53") (name "Net-(U$15-RXCAN)") (class "Default")
      (node (ref "U$15") (pin "2") (pinfunction "RXCAN_2") (pintype "bidirectional"))
      (node (ref "U$16") (pin "4") (pinfunction "RXD_4") (pintype "bidirectional"))
    )
    (net (code "54") (name "Net-(U$15-TXCAN)") (class "Default")
      (node (ref "U$15") (pin "1") (pinfunction "TXCAN_1") (pintype "bidirectional"))
      (node (ref "U$16") (pin "1") (pinfunction "TXD_1") (pintype "bidirectional"))
    )
    (net (code "55") (name "Net-(U$19-RXCAN)") (class "Default")
      (node (ref "U$19") (pin "2") (pinfunction "RXCAN_2") (pintype "bidirectional"))
      (node (ref "U$20") (pin "4") (pinfunction "RXD_4") (pintype "bidirectional"))
    )
    (net (code "56") (name "Net-(U$19-TXCAN)") (class "Default")
      (node (ref "U$19") (pin "1") (pinfunction "TXCAN_1") (pintype "bidirectional"))
      (node (ref "U$20") (pin "1") (pinfunction "TXD_1") (pintype "bidirectional"))
    )
    (net (code "57") (name "unconnected-(U$3-INT0{slash}-Pad9)") (class "Default")
      (node (ref "U$3") (pin "9") (pinfunction "INT0/_9") (pintype "bidirectional"))
    )
    (net (code "58") (name "unconnected-(U$3-INT1{slash}-Pad8)") (class "Default")
      (node (ref "U$3") (pin "8") (pinfunction "INT1/_8") (pintype "bidirectional"))
    )
    (net (code "59") (name "unconnected-(U$3-INT{slash}-Pad4)") (class "Default")
      (node (ref "U$3") (pin "4") (pinfunction "INT/_4") (pintype "bidirectional"))
    )
    (net (code "60") (name "unconnected-(U$4-STBY-Pad8)") (class "Default")
      (node (ref "U$4") (pin "8") (pinfunction "STBY_8") (pintype "bidirectional"))
    )
    (net (code "61") (name "unconnected-(U$5-INT0{slash}-Pad9)") (class "Default")
      (node (ref "U$5") (pin "9") (pinfunction "INT0/_9") (pintype "bidirectional"))
    )
    (net (code "62") (name "unconnected-(U$5-INT1{slash}-Pad8)") (class "Default")
      (node (ref "U$5") (pin "8") (pinfunction "INT1/_8") (pintype "bidirectional"))
    )
    (net (code "63") (name "unconnected-(U$5-INT{slash}-Pad4)") (class "Default")
      (node (ref "U$5") (pin "4") (pinfunction "INT/_4") (pintype "bidirectional"))
    )
    (net (code "64") (name "unconnected-(U$5-OCS2-Pad5)") (class "Default")
      (node (ref "U$5") (pin "5") (pinfunction "OCS2_5") (pintype "bidirectional"))
    )
    (net (code "65") (name "unconnected-(U$6-STBY-Pad8)") (class "Default")
      (node (ref "U$6") (pin "8") (pinfunction "STBY_8") (pintype "bidirectional"))
    )
    (net (code "66") (name "unconnected-(U$7-INT0{slash}-Pad9)") (class "Default")
      (node (ref "U$7") (pin "9") (pinfunction "INT0/_9") (pintype "bidirectional"))
    )
    (net (code "67") (name "unconnected-(U$7-INT1{slash}-Pad8)") (class "Default")
      (node (ref "U$7") (pin "8") (pinfunction "INT1/_8") (pintype "bidirectional"))
    )
    (net (code "68") (name "unconnected-(U$7-INT{slash}-Pad4)") (class "Default")
      (node (ref "U$7") (pin "4") (pinfunction "INT/_4") (pintype "bidirectional"))
    )
    (net (code "69") (name "unconnected-(U$7-OCS2-Pad5)") (class "Default")
      (node (ref "U$7") (pin "5") (pinfunction "OCS2_5") (pintype "bidirectional"))
    )
    (net (code "70") (name "unconnected-(U$8-STBY-Pad8)") (class "Default")
      (node (ref "U$8") (pin "8") (pinfunction "STBY_8") (pintype "bidirectional"))
    )
    (net (code "71") (name "unconnected-(U$9-INT0{slash}-Pad9)") (class "Default")
      (node (ref "U$9") (pin "9") (pinfunction "INT0/_9") (pintype "bidirectional"))
    )
    (net (code "72") (name "unconnected-(U$9-INT1{slash}-Pad8)") (class "Default")
      (node (ref "U$9") (pin "8") (pinfunction "INT1/_8") (pintype "bidirectional"))
    )
    (net (code "73") (name "unconnected-(U$9-INT{slash}-Pad4)") (class "Default")
      (node (ref "U$9") (pin "4") (pinfunction "INT/_4") (pintype "bidirectional"))
    )
    (net (code "74") (name "unconnected-(U$9-OCS2-Pad5)") (class "Default")
      (node (ref "U$9") (pin "5") (pinfunction "OCS2_5") (pintype "bidirectional"))
    )
    (net (code "75") (name "unconnected-(U$10-STBY-Pad8)") (class "Default")
      (node (ref "U$10") (pin "8") (pinfunction "STBY_8") (pintype "bidirectional"))
    )
    (net (code "76") (name "unconnected-(U$11-INT0{slash}-Pad9)") (class "Default")
      (node (ref "U$11") (pin "9") (pinfunction "INT0/_9") (pintype "bidirectional"))
    )
    (net (code "77") (name "unconnected-(U$11-INT1{slash}-Pad8)") (class "Default")
      (node (ref "U$11") (pin "8") (pinfunction "INT1/_8") (pintype "bidirectional"))
    )
    (net (code "78") (name "unconnected-(U$11-INT{slash}-Pad4)") (class "Default")
      (node (ref "U$11") (pin "4") (pinfunction "INT/_4") (pintype "bidirectional"))
    )
    (net (code "79") (name "unconnected-(U$11-OCS2-Pad5)") (class "Default")
      (node (ref "U$11") (pin "5") (pinfunction "OCS2_5") (pintype "bidirectional"))
    )
    (net (code "80") (name "unconnected-(U$12-STBY-Pad8)") (class "Default")
      (node (ref "U$12") (pin "8") (pinfunction "STBY_8") (pintype "bidirectional"))
    )
    (net (code "81") (name "unconnected-(U$13-INT0{slash}-Pad9)") (class "Default")
      (node (ref "U$13") (pin "9") (pinfunction "INT0/_9") (pintype "bidirectional"))
    )
    (net (code "82") (name "unconnected-(U$13-INT1{slash}-Pad8)") (class "Default")
      (node (ref "U$13") (pin "8") (pinfunction "INT1/_8") (pintype "bidirectional"))
    )
    (net (code "83") (name "unconnected-(U$13-INT{slash}-Pad4)") (class "Default")
      (node (ref "U$13") (pin "4") (pinfunction "INT/_4") (pintype "bidirectional"))
    )
    (net (code "84") (name "unconnected-(U$13-OCS2-Pad5)") (class "Default")
      (node (ref "U$13") (pin "5") (pinfunction "OCS2_5") (pintype "bidirectional"))
    )
    (net (code "85") (name "unconnected-(U$14-STBY-Pad8)") (class "Default")
      (node (ref "U$14") (pin "8") (pinfunction "STBY_8") (pintype "bidirectional"))
    )
    (net (code "86") (name "unconnected-(U$15-INT0{slash}-Pad9)") (class "Default")
      (node (ref "U$15") (pin "9") (pinfunction "INT0/_9") (pintype "bidirectional"))
    )
    (net (code "87") (name "unconnected-(U$15-INT1{slash}-Pad8)") (class "Default")
      (node (ref "U$15") (pin "8") (pinfunction "INT1/_8") (pintype "bidirectional"))
    )
    (net (code "88") (name "unconnected-(U$15-INT{slash}-Pad4)") (class "Default")
      (node (ref "U$15") (pin "4") (pinfunction "INT/_4") (pintype "bidirectional"))
    )
    (net (code "89") (name "unconnected-(U$15-OCS2-Pad5)") (class "Default")
      (node (ref "U$15") (pin "5") (pinfunction "OCS2_5") (pintype "bidirectional"))
    )
    (net (code "90") (name "unconnected-(U$16-STBY-Pad8)") (class "Default")
      (node (ref "U$16") (pin "8") (pinfunction "STBY_8") (pintype "bidirectional"))
    )
    (net (code "91") (name "unconnected-(U$19-INT0{slash}-Pad9)") (class "Default")
      (node (ref "U$19") (pin "9") (pinfunction "INT0/_9") (pintype "bidirectional"))
    )
    (net (code "92") (name "unconnected-(U$19-INT1{slash}-Pad8)") (class "Default")
      (node (ref "U$19") (pin "8") (pinfunction "INT1/_8") (pintype "bidirectional"))
    )
    (net (code "93") (name "unconnected-(U$19-INT{slash}-Pad4)") (class "Default")
      (node (ref "U$19") (pin "4") (pinfunction "INT/_4") (pintype "bidirectional"))
    )
    (net (code "94") (name "unconnected-(U$19-OCS2-Pad5)") (class "Default")
      (node (ref "U$19") (pin "5") (pinfunction "OCS2_5") (pintype "bidirectional"))
    )
    (net (code "95") (name "unconnected-(U$20-STBY-Pad8)") (class "Default")
      (node (ref "U$20") (pin "8") (pinfunction "STBY_8") (pintype "bidirectional"))
    )
  )
)
